# power.net
KiCad netlist of a schematic drawn in Altium Designer
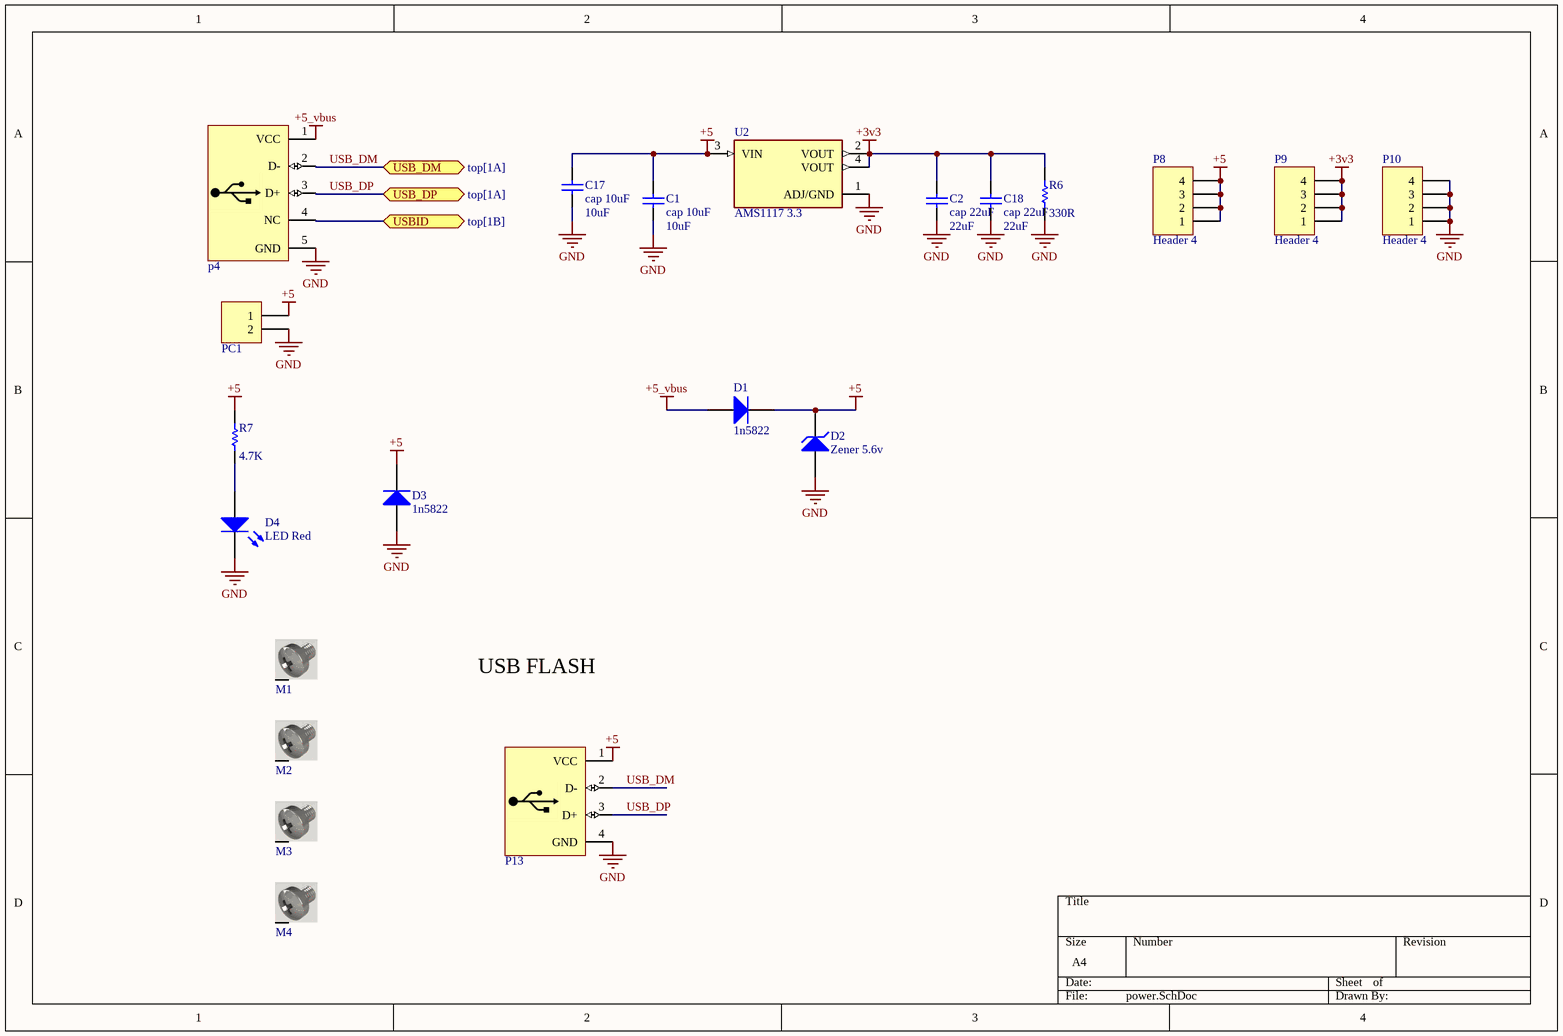
[diagram p0: power.SchDoc]

(export (version "E")
  (design (tool "Eeschema 10.0.6"))
  (components
    (comp (ref "C1")
      (value "cap 10uF")
      (footprint "Cap 805")
      (description "Capacitor")
      (fields (field (name "ALTIUM_VALUE") "10uF") (field (name "PUBLISHER") "Altium Limited"))
      (libsource (lib "Miscellaneous Devices") (part "Cap"))
    )
    (comp (ref "C2")
      (value "cap 22uF")
      (footprint "Cap 805")
      (description "Capacitor")
      (fields (field (name "ALTIUM_VALUE") "22uF") (field (name "PUBLISHER") "Altium Limited"))
      (libsource (lib "Miscellaneous Devices") (part "Cap"))
    )
    (comp (ref "C17")
      (value "cap 10uF")
      (footprint "Cap 805")
      (description "Capacitor")
      (fields (field (name "ALTIUM_VALUE") "10uF") (field (name "PUBLISHER") "Altium Limited"))
      (libsource (lib "Miscellaneous Devices") (part "Cap"))
    )
    (comp (ref "C18")
      (value "cap 22uF")
      (footprint "Cap 805")
      (description "Capacitor")
      (fields (field (name "ALTIUM_VALUE") "22uF") (field (name "PUBLISHER") "Altium Limited"))
      (libsource (lib "Miscellaneous Devices") (part "Cap"))
    )
    (comp (ref "D1")
      (value "1n5822")
      (footprint "SMA DIODE 2")
      (description "1 Amp schottky Diode")
      (fields (field (name "PUBLISHER") "Altium Limited"))
      (libsource (lib "Miscellaneous Devices") (part "Diode 1N4007"))
    )
    (comp (ref "D2")
      (value "Zener 5.6v")
      (footprint "Diode 1n4148 SMD")
      (description "Zener Diode")
      (fields (field (name "PUBLISHER") "Altium Limited"))
      (libsource (lib "Miscellaneous Devices") (part "D Zener"))
    )
    (comp (ref "D3")
      (value "1n5822")
      (footprint "SMA DIODE 2")
      (description "1 Amp schottky Diode")
      (fields (field (name "PUBLISHER") "Altium Limited"))
      (libsource (lib "Miscellaneous Devices") (part "Diode 1N4007"))
    )
    (comp (ref "D4")
      (value "LED Red")
      (footprint "0805-LED")
      (description "LED SMD")
      (fields (field (name "PUBLISHER") "Altium Limited"))
      (libsource (lib "Miscellaneous Devices") (part "LED0"))
    )
    (comp (ref "M1")
      (value "Spacer-ff 10mm")
      (footprint "Screw")
      (description "Board Screw With Spacer")
      (libsource (lib "My Library") (part "Board Screw"))
    )
    (comp (ref "M2")
      (value "Spacer-ff 10mm")
      (footprint "screw")
      (description "Board Screw With Spacer")
      (libsource (lib "My Library") (part "Board Screw"))
    )
    (comp (ref "M3")
      (value "Spacer-ff 10mm")
      (footprint "screw")
      (description "Board Screw With Spacer")
      (libsource (lib "My Library") (part "Board Screw"))
    )
    (comp (ref "M4")
      (value "Spacer-ff 10mm")
      (footprint "screw")
      (description "Board Screw With Spacer")
      (libsource (lib "My Library") (part "Board Screw"))
    )
    (comp (ref "p4")
      (value "USB Connector")
      (footprint "USB_AB_BM_SHS")
      (description "USB Connector MICRO-B Type")
      (fields (field (name "DESIGNER") "ABBAS BASEREH") (field (name "PUBLISHER") "ABBAS BASEREH"))
      (libsource (lib "Altium (2)") (part "USB MICRO"))
    )
    (comp (ref "P8")
      (value "Header 4")
      (footprint "HDR1X4")
      (description "Header, 4-Pin")
      (fields (field (name "PUBLISHER") "Altium Limited"))
      (libsource (lib "Miscellaneous Connectors") (part "Header 4"))
    )
    (comp (ref "P9")
      (value "Header 4")
      (footprint "HDR1X4")
      (description "Header, 4-Pin")
      (fields (field (name "PUBLISHER") "Altium Limited"))
      (libsource (lib "Miscellaneous Connectors") (part "Header 4"))
    )
    (comp (ref "P10")
      (value "Header 4")
      (footprint "HDR1X4")
      (description "Header, 4-Pin")
      (fields (field (name "PUBLISHER") "Altium Limited"))
      (libsource (lib "Miscellaneous Connectors") (part "Header 4"))
    )
    (comp (ref "P13")
      (value "USB Connector A Type Femal")
      (footprint "USB2.5-2H4C")
      (description "USB Connector-A Type Femal")
      (libsource (lib "Altium (2)") (part "USB A-Type"))
    )
    (comp (ref "PC1")
      (value "Power Connector")
      (footprint "My_ Power_Connector")
      (description "white Power Connector")
      (libsource (lib "Altium library (www.AVRelec.com)") (part "Power Connector"))
    )
    (comp (ref "R6")
      (value "330R")
      (footprint "RES 0805 (2012X06L)")
      (description "Resistor")
      (fields (field (name "Comment") "Res 330R") (field (name "PUBLISHER") "Altium Limited"))
      (libsource (lib "Miscellaneous Devices") (part "Res1"))
    )
    (comp (ref "R7")
      (value "4.7K")
      (footprint "RES 0805 (2012X06L)")
      (description "Resistor")
      (fields (field (name "Comment") "Res 4.7K") (field (name "PUBLISHER") "Altium Limited"))
      (libsource (lib "Miscellaneous Devices") (part "Res1"))
    )
    (comp (ref "U2")
      (value "AMS1117 3.3")
      (footprint "SOT223")
      (fields (field (name "MP") "AMS1117") (field (name "MF") "Seeed Technology"))
      (libsource (lib "AMS1117") (part "AMS1117"))
    )
  )
  (nets
    (net (code "1") (name "+3v3") (class "Default")
      (node (ref "C18") (pin "2") (pinfunction "2_2") (pintype "passive"))
      (node (ref "C2") (pin "2") (pinfunction "2_2") (pintype "passive"))
      (node (ref "P9") (pin "1") (pinfunction "1_1") (pintype "passive"))
      (node (ref "P9") (pin "2") (pinfunction "2_2") (pintype "passive"))
      (node (ref "P9") (pin "3") (pinfunction "3_3") (pintype "passive"))
      (node (ref "P9") (pin "4") (pinfunction "4_4") (pintype "passive"))
      (node (ref "R6") (pin "2") (pinfunction "2_2") (pintype "passive"))
      (node (ref "U2") (pin "2") (pinfunction "VOUT_2") (pintype "output"))
      (node (ref "U2") (pin "4") (pinfunction "VOUT_4") (pintype "output"))
    )
    (net (code "2") (name "+5") (class "Default")
      (node (ref "C1") (pin "2") (pinfunction "2_2") (pintype "passive"))
      (node (ref "C17") (pin "2") (pinfunction "2_2") (pintype "passive"))
      (node (ref "D1") (pin "2") (pinfunction "K_2") (pintype "passive"))
      (node (ref "D2") (pin "2") (pinfunction "K_2") (pintype "passive"))
      (node (ref "D3") (pin "2") (pinfunction "K_2") (pintype "passive"))
      (node (ref "P13") (pin "1") (pinfunction "VCC_1") (pintype "power_in"))
      (node (ref "P8") (pin "1") (pinfunction "1_1") (pintype "passive"))
      (node (ref "P8") (pin "2") (pinfunction "2_2") (pintype "passive"))
      (node (ref "P8") (pin "3") (pinfunction "3_3") (pintype "passive"))
      (node (ref "P8") (pin "4") (pinfunction "4_4") (pintype "passive"))
      (node (ref "PC1") (pin "1") (pinfunction "1_1") (pintype "passive"))
      (node (ref "R7") (pin "2") (pinfunction "2_2") (pintype "passive"))
      (node (ref "U2") (pin "3") (pinfunction "VIN_3") (pintype "input"))
    )
    (net (code "3") (name "+5_vbus") (class "Default")
      (node (ref "D1") (pin "1") (pinfunction "A_1") (pintype "passive"))
      (node (ref "p4") (pin "1") (pinfunction "VCC_1") (pintype "power_in"))
    )
    (net (code "4") (name "/USBID") (class "Default")
      (node (ref "p4") (pin "4") (pinfunction "NC_4") (pintype "passive"))
    )
    (net (code "5") (name "/USB_DM") (class "Default")
      (node (ref "P13") (pin "2") (pinfunction "D-_2") (pintype "bidirectional"))
      (node (ref "p4") (pin "2") (pinfunction "D-_2") (pintype "bidirectional"))
    )
    (net (code "6") (name "/USB_DP") (class "Default")
      (node (ref "P13") (pin "3") (pinfunction "D+_3") (pintype "bidirectional"))
      (node (ref "p4") (pin "3") (pinfunction "D+_3") (pintype "bidirectional"))
    )
    (net (code "7") (name "GND") (class "Default")
      (node (ref "C1") (pin "1") (pinfunction "1_1") (pintype "passive"))
      (node (ref "C17") (pin "1") (pinfunction "1_1") (pintype "passive"))
      (node (ref "C18") (pin "1") (pinfunction "1_1") (pintype "passive"))
      (node (ref "C2") (pin "1") (pinfunction "1_1") (pintype "passive"))
      (node (ref "D2") (pin "1") (pinfunction "A_1") (pintype "passive"))
      (node (ref "D3") (pin "1") (pinfunction "A_1") (pintype "passive"))
      (node (ref "D4") (pin "2") (pinfunction "K_2") (pintype "passive"))
      (node (ref "P10") (pin "1") (pinfunction "1_1") (pintype "passive"))
      (node (ref "P10") (pin "2") (pinfunction "2_2") (pintype "passive"))
      (node (ref "P10") (pin "3") (pinfunction "3_3") (pintype "passive"))
      (node (ref "P10") (pin "4") (pinfunction "4_4") (pintype "passive"))
      (node (ref "P13") (pin "4") (pinfunction "GND_4") (pintype "power_in"))
      (node (ref "PC1") (pin "2") (pinfunction "2_2") (pintype "passive"))
      (node (ref "R6") (pin "1") (pinfunction "1_1") (pintype "passive"))
      (node (ref "U2") (pin "1") (pinfunction "ADJ/GND_1") (pintype "power_in"))
      (node (ref "p4") (pin "5") (pinfunction "GND_5") (pintype "power_in"))
    )
    (net (code "8") (name "Net-(D4-A)") (class "Default")
      (node (ref "D4") (pin "1") (pinfunction "A_1") (pintype "passive"))
      (node (ref "R7") (pin "1") (pinfunction "1_1") (pintype "passive"))
    )
    (net (code "9") (name "unconnected-(M1-PadS)") (class "Default")
      (node (ref "M1") (pin "S") (pinfunction "S_S") (pintype "passive"))
    )
    (net (code "10") (name "unconnected-(M2-PadS)") (class "Default")
      (node (ref "M2") (pin "S") (pinfunction "S_S") (pintype "passive"))
    )
    (net (code "11") (name "unconnected-(M3-PadS)") (class "Default")
      (node (ref "M3") (pin "S") (pinfunction "S_S") (pintype "passive"))
    )
    (net (code "12") (name "unconnected-(M4-PadS)") (class "Default")
      (node (ref "M4") (pin "S") (pinfunction "S_S") (pintype "passive"))
    )
  )
)
